# brightness-control.net
KiCad netlist of a schematic drawn in EAGLE
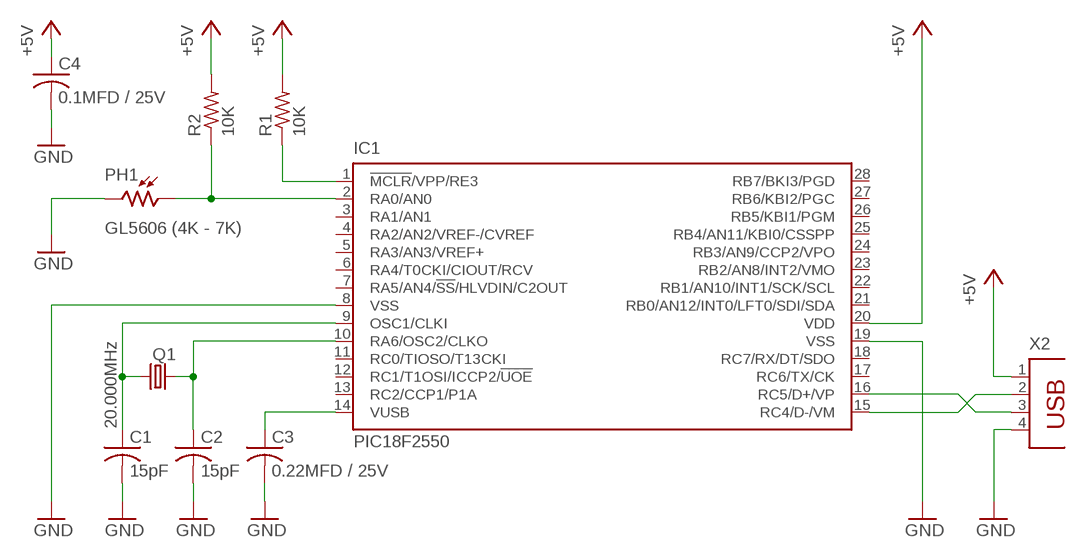
[diagram p0: schematic, sheet 1]

(export (version "E")
  (design (tool "Eeschema 10.0.6"))
  (components
    (comp (ref "C1")
      (value "15pF")
      (footprint "eagle-import:C050-024X044")
      (libsource (lib "eagle-import") (part "C-US050-024X044"))
    )
    (comp (ref "C2")
      (value "15pF")
      (footprint "eagle-import:C050-024X044")
      (libsource (lib "eagle-import") (part "C-US050-024X044"))
    )
    (comp (ref "C3")
      (value "0.22MFD / 25V")
      (footprint "eagle-import:C050-055X075")
      (libsource (lib "eagle-import") (part "C-US050-055X075"))
    )
    (comp (ref "C4")
      (value "0.1MFD / 25V")
      (footprint "eagle-import:C050-045X075")
      (libsource (lib "eagle-import") (part "C-US050-045X075"))
    )
    (comp (ref "IC1")
      (value "PIC18F2550")
      (footprint "eagle-import:DIL28-3")
      (fields (field (name "MF") "MICROCHIP") (field (name "MPN") "PIC18F2550-I/SP"))
      (libsource (lib "eagle-import") (part "PIC18F2_28DIP550"))
    )
    (comp (ref "PH1")
      (value "GL5606 (4K - 7K)")
      (footprint "eagle-import:TO-5_V10")
      (libsource (lib "eagle-import") (part "?1060V_21"))
    )
    (comp (ref "Q1")
      (value "20.000MHz")
      (footprint "eagle-import:HC49U-LM")
      (libsource (lib "eagle-import") (part "CRYSTALHC49U-LM"))
    )
    (comp (ref "R1")
      (value "10K")
      (footprint "eagle-import:0207_10")
      (libsource (lib "eagle-import") (part "R-US_0207/10"))
    )
    (comp (ref "R2")
      (value "10K")
      (footprint "eagle-import:0207_10")
      (libsource (lib "eagle-import") (part "R-US_0207/10"))
    )
    (comp (ref "X2")
      (value "PN61729")
      (footprint "eagle-import:PN61729")
      (libsource (lib "eagle-import") (part "PN61729"))
    )
  )
  (nets
    (net (code "1") (name "+5V") (class "Default")
      (node (ref "C4") (pin "1") (pinfunction "1_1") (pintype "passive"))
      (node (ref "IC1") (pin "20") (pinfunction "VDD_20") (pintype "power_in"))
      (node (ref "R1") (pin "2") (pinfunction "2_2") (pintype "passive"))
      (node (ref "R2") (pin "2") (pinfunction "2_2") (pintype "passive"))
      (node (ref "X2") (pin "1") (pinfunction "1_1") (pintype "passive"))
    )
    (net (code "2") (name "GND") (class "Default")
      (node (ref "C1") (pin "2") (pinfunction "2_2") (pintype "passive"))
      (node (ref "C2") (pin "2") (pinfunction "2_2") (pintype "passive"))
      (node (ref "C3") (pin "2") (pinfunction "2_2") (pintype "passive"))
      (node (ref "C4") (pin "2") (pinfunction "2_2") (pintype "passive"))
      (node (ref "IC1") (pin "19") (pinfunction "VSS_19") (pintype "power_in"))
      (node (ref "IC1") (pin "8") (pinfunction "VSS_8") (pintype "power_in"))
      (node (ref "PH1") (pin "2") (pinfunction "2_2") (pintype "passive"))
      (node (ref "X2") (pin "4") (pinfunction "4_4") (pintype "passive"))
    )
    (net (code "3") (name "Net-(IC1-OSC1{slash}CLKI)") (class "Default")
      (node (ref "C1") (pin "1") (pinfunction "1_1") (pintype "passive"))
      (node (ref "IC1") (pin "9") (pinfunction "OSC1/CLKI_9") (pintype "input"))
      (node (ref "Q1") (pin "2") (pinfunction "2_2") (pintype "passive"))
    )
    (net (code "4") (name "Net-(IC1-RA0{slash}AN0)") (class "Default")
      (node (ref "IC1") (pin "2") (pinfunction "RA0/AN0_2") (pintype "bidirectional"))
      (node (ref "PH1") (pin "1") (pinfunction "1_1") (pintype "passive"))
      (node (ref "R2") (pin "1") (pinfunction "1_1") (pintype "passive"))
    )
    (net (code "5") (name "Net-(IC1-RA6{slash}OSC2{slash}CLKO)") (class "Default")
      (node (ref "C2") (pin "1") (pinfunction "1_1") (pintype "passive"))
      (node (ref "IC1") (pin "10") (pinfunction "RA6/OSC2/CLKO_10") (pintype "output"))
      (node (ref "Q1") (pin "1") (pinfunction "1_1") (pintype "passive"))
    )
    (net (code "6") (name "Net-(IC1-RC4{slash}D-{slash}VM)") (class "Default")
      (node (ref "IC1") (pin "15") (pinfunction "RC4/D-/VM_15") (pintype "bidirectional"))
      (node (ref "X2") (pin "2") (pinfunction "2_2") (pintype "passive"))
    )
    (net (code "7") (name "Net-(IC1-RC5{slash}D+{slash}VP)") (class "Default")
      (node (ref "IC1") (pin "16") (pinfunction "RC5/D+/VP_16") (pintype "bidirectional"))
      (node (ref "X2") (pin "3") (pinfunction "3_3") (pintype "passive"))
    )
    (net (code "8") (name "Net-(IC1-VUSB)") (class "Default")
      (node (ref "C3") (pin "1") (pinfunction "1_1") (pintype "passive"))
      (node (ref "IC1") (pin "14") (pinfunction "VUSB_14") (pintype "bidirectional"))
    )
    (net (code "9") (name "Net-(IC1-~{MCLR}{slash}VPP{slash}RE3)") (class "Default")
      (node (ref "IC1") (pin "1") (pinfunction "~{MCLR}/VPP/RE3_1") (pintype "input"))
      (node (ref "R1") (pin "1") (pinfunction "1_1") (pintype "passive"))
    )
    (net (code "10") (name "unconnected-(IC1-RA1{slash}AN1-Pad3)") (class "Default")
      (node (ref "IC1") (pin "3") (pinfunction "RA1/AN1_3") (pintype "bidirectional"))
    )
    (net (code "11") (name "unconnected-(IC1-RA2{slash}AN2{slash}VREF-{slash}CVREF-Pad4)") (class "Default")
      (node (ref "IC1") (pin "4") (pinfunction "RA2/AN2/VREF-/CVREF_4") (pintype "bidirectional"))
    )
    (net (code "12") (name "unconnected-(IC1-RA3{slash}AN3{slash}VREF+-Pad5)") (class "Default")
      (node (ref "IC1") (pin "5") (pinfunction "RA3/AN3/VREF+_5") (pintype "bidirectional"))
    )
    (net (code "13") (name "unconnected-(IC1-RA4{slash}T0CKI{slash}CIOUT{slash}RCV-Pad6)") (class "Default")
      (node (ref "IC1") (pin "6") (pinfunction "RA4/T0CKI/CIOUT/RCV_6") (pintype "bidirectional"))
    )
    (net (code "14") (name "unconnected-(IC1-RA5{slash}AN4{slash}~{SS}{slash}HLVDIN{slash}C2OUT-Pad7)") (class "Default")
      (node (ref "IC1") (pin "7") (pinfunction "RA5/AN4/~{SS}/HLVDIN/C2OUT_7") (pintype "bidirectional"))
    )
    (net (code "15") (name "unconnected-(IC1-RB0{slash}AN12{slash}INT0{slash}LFT0{slash}SDI{slash}SDA-Pad21)") (class "Default")
      (node (ref "IC1") (pin "21") (pinfunction "RB0/AN12/INT0/LFT0/SDI/SDA_21") (pintype "bidirectional"))
    )
    (net (code "16") (name "unconnected-(IC1-RB1{slash}AN10{slash}INT1{slash}SCK{slash}SCL-Pad22)") (class "Default")
      (node (ref "IC1") (pin "22") (pinfunction "RB1/AN10/INT1/SCK/SCL_22") (pintype "bidirectional"))
    )
    (net (code "17") (name "unconnected-(IC1-RB2{slash}AN8{slash}INT2{slash}VMO-Pad23)") (class "Default")
      (node (ref "IC1") (pin "23") (pinfunction "RB2/AN8/INT2/VMO_23") (pintype "bidirectional"))
    )
    (net (code "18") (name "unconnected-(IC1-RB3{slash}AN9{slash}CCP2{slash}VPO-Pad24)") (class "Default")
      (node (ref "IC1") (pin "24") (pinfunction "RB3/AN9/CCP2/VPO_24") (pintype "bidirectional"))
    )
    (net (code "19") (name "unconnected-(IC1-RB4{slash}AN11{slash}KBI0{slash}CSSPP-Pad25)") (class "Default")
      (node (ref "IC1") (pin "25") (pinfunction "RB4/AN11/KBI0/CSSPP_25") (pintype "bidirectional"))
    )
    (net (code "20") (name "unconnected-(IC1-RB5{slash}KBI1{slash}PGM-Pad26)") (class "Default")
      (node (ref "IC1") (pin "26") (pinfunction "RB5/KBI1/PGM_26") (pintype "bidirectional"))
    )
    (net (code "21") (name "unconnected-(IC1-RB6{slash}KBI2{slash}PGC-Pad27)") (class "Default")
      (node (ref "IC1") (pin "27") (pinfunction "RB6/KBI2/PGC_27") (pintype "bidirectional"))
    )
    (net (code "22") (name "unconnected-(IC1-RB7{slash}BKI3{slash}PGD-Pad28)") (class "Default")
      (node (ref "IC1") (pin "28") (pinfunction "RB7/BKI3/PGD_28") (pintype "bidirectional"))
    )
    (net (code "23") (name "unconnected-(IC1-RC0{slash}TIOSO{slash}T13CKI-Pad11)") (class "Default")
      (node (ref "IC1") (pin "11") (pinfunction "RC0/TIOSO/T13CKI_11") (pintype "bidirectional"))
    )
    (net (code "24") (name "unconnected-(IC1-RC1{slash}T1OSI{slash}ICCP2{slash}~{UOE}-Pad12)") (class "Default")
      (node (ref "IC1") (pin "12") (pinfunction "RC1/T1OSI/ICCP2/~{UOE}_12") (pintype "bidirectional"))
    )
    (net (code "25") (name "unconnected-(IC1-RC2{slash}CCP1{slash}P1A-Pad13)") (class "Default")
      (node (ref "IC1") (pin "13") (pinfunction "RC2/CCP1/P1A_13") (pintype "bidirectional"))
    )
    (net (code "26") (name "unconnected-(IC1-RC6{slash}TX{slash}CK-Pad17)") (class "Default")
      (node (ref "IC1") (pin "17") (pinfunction "RC6/TX/CK_17") (pintype "bidirectional"))
    )
    (net (code "27") (name "unconnected-(IC1-RC7{slash}RX{slash}DT{slash}SDO-Pad18)") (class "Default")
      (node (ref "IC1") (pin "18") (pinfunction "RC7/RX/DT/SDO_18") (pintype "bidirectional"))
    )
  )
)
